# cs301_template.net
KiCad netlist of a schematic drawn in Altium Designer
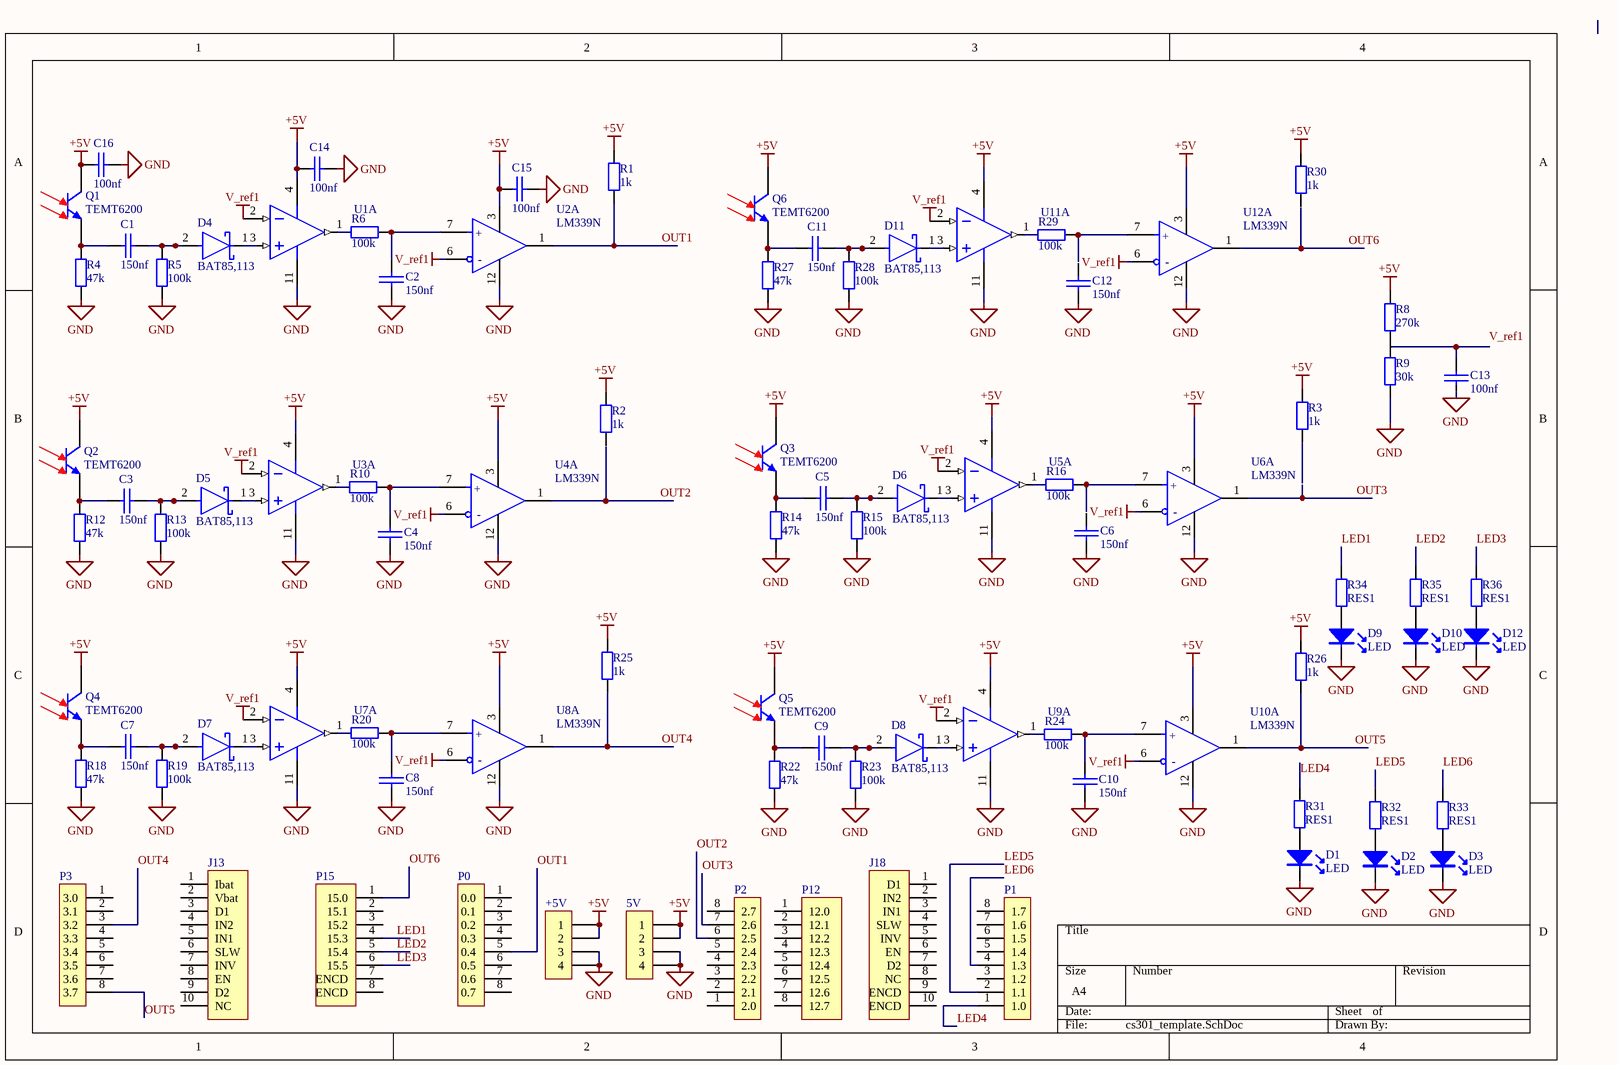
[diagram p0: cs301_template.SchDoc]

(export (version "E")
  (design (tool "Eeschema 10.0.6"))
  (components
    (comp (ref "+5V")
      (value "5V")
      (footprint "IDC4")
      (description "Connector")
      (libsource (lib "Miscellaneous Devices") (part "CON4"))
    )
    (comp (ref "5V")
      (value "5V")
      (footprint "IDC4")
      (description "Connector")
      (libsource (lib "Miscellaneous Devices") (part "CON4"))
    )
    (comp (ref "C1")
      (value "150nf")
      (footprint "CCAP-5P0")
      (description "TH ceramic capacitor with 5mm pitch")
      (libsource (lib "COMSYS301_2025") (part "CerCap_TH_5P0"))
    )
    (comp (ref "C2")
      (value "150nf")
      (footprint "CCAP-5P0")
      (description "TH ceramic capacitor with 5mm pitch")
      (libsource (lib "COMSYS301_2025") (part "CerCap_TH_5P0"))
    )
    (comp (ref "C3")
      (value "150nf")
      (footprint "CCAP-5P0")
      (description "TH ceramic capacitor with 5mm pitch")
      (libsource (lib "COMSYS301_2025") (part "CerCap_TH_5P0"))
    )
    (comp (ref "C4")
      (value "150nf")
      (footprint "CCAP-5P0")
      (description "TH ceramic capacitor with 5mm pitch")
      (libsource (lib "COMSYS301_2025") (part "CerCap_TH_5P0"))
    )
    (comp (ref "C5")
      (value "150nf")
      (footprint "CCAP-5P0")
      (description "TH ceramic capacitor with 5mm pitch")
      (libsource (lib "COMSYS301_2025") (part "CerCap_TH_5P0"))
    )
    (comp (ref "C6")
      (value "150nf")
      (footprint "CCAP-5P0")
      (description "TH ceramic capacitor with 5mm pitch")
      (libsource (lib "COMSYS301_2025") (part "CerCap_TH_5P0"))
    )
    (comp (ref "C7")
      (value "150nf")
      (footprint "CCAP-5P0")
      (description "TH ceramic capacitor with 5mm pitch")
      (libsource (lib "COMSYS301_2025") (part "CerCap_TH_5P0"))
    )
    (comp (ref "C8")
      (value "150nf")
      (footprint "CCAP-5P0")
      (description "TH ceramic capacitor with 5mm pitch")
      (libsource (lib "COMSYS301_2025") (part "CerCap_TH_5P0"))
    )
    (comp (ref "C9")
      (value "150nf")
      (footprint "CCAP-5P0")
      (description "TH ceramic capacitor with 5mm pitch")
      (libsource (lib "COMSYS301_2025") (part "CerCap_TH_5P0"))
    )
    (comp (ref "C10")
      (value "150nf")
      (footprint "CCAP-5P0")
      (description "TH ceramic capacitor with 5mm pitch")
      (libsource (lib "COMSYS301_2025") (part "CerCap_TH_5P0"))
    )
    (comp (ref "C11")
      (value "150nf")
      (footprint "CCAP-5P0")
      (description "TH ceramic capacitor with 5mm pitch")
      (libsource (lib "COMSYS301_2025") (part "CerCap_TH_5P0"))
    )
    (comp (ref "C12")
      (value "150nf")
      (footprint "CCAP-5P0")
      (description "TH ceramic capacitor with 5mm pitch")
      (libsource (lib "COMSYS301_2025") (part "CerCap_TH_5P0"))
    )
    (comp (ref "C13")
      (value "100nf")
      (footprint "CCAP-5P0")
      (description "TH ceramic capacitor with 5mm pitch")
      (libsource (lib "COMSYS301_2025") (part "CerCap_TH_5P0"))
    )
    (comp (ref "C14")
      (value "100nf")
      (footprint "CCAP-5P0")
      (description "TH ceramic capacitor with 5mm pitch")
      (libsource (lib "COMSYS301_2025") (part "CerCap_TH_5P0"))
    )
    (comp (ref "C15")
      (value "100nf")
      (footprint "CCAP-5P0")
      (description "TH ceramic capacitor with 5mm pitch")
      (libsource (lib "COMSYS301_2025") (part "CerCap_TH_5P0"))
    )
    (comp (ref "C16")
      (value "100nf")
      (footprint "CCAP-5P0")
      (description "TH ceramic capacitor with 5mm pitch")
      (libsource (lib "COMSYS301_2025") (part "CerCap_TH_5P0"))
    )
    (comp (ref "D1") (value "LED") (footprint "LED0.1/5MM") (libsource (lib "COMSYS301_2013") (part "LED")))
    (comp (ref "D2") (value "LED") (footprint "LED0.1/5MM") (libsource (lib "COMSYS301_2013") (part "LED")))
    (comp (ref "D3") (value "LED") (footprint "LED0.1/5MM") (libsource (lib "COMSYS301_2013") (part "LED")))
    (comp (ref "D4")
      (value "BAT85,113")
      (footprint "FP-SOD68-MFG")
      (description "DIODE SCHOTTKY 30V 200MA DO34")
      (libsource (lib "Components - 18.08.25 - 15.16") (part "CMP-14398-000042-1"))
    )
    (comp (ref "D5")
      (value "BAT85,113")
      (footprint "FP-SOD68-MFG")
      (description "DIODE SCHOTTKY 30V 200MA DO34")
      (libsource (lib "Components - 18.08.25 - 15.16") (part "CMP-14398-000042-1"))
    )
    (comp (ref "D6")
      (value "BAT85,113")
      (footprint "FP-SOD68-MFG")
      (description "DIODE SCHOTTKY 30V 200MA DO34")
      (libsource (lib "Components - 18.08.25 - 15.16") (part "CMP-14398-000042-1"))
    )
    (comp (ref "D7")
      (value "BAT85,113")
      (footprint "FP-SOD68-MFG")
      (description "DIODE SCHOTTKY 30V 200MA DO34")
      (libsource (lib "Components - 18.08.25 - 15.16") (part "CMP-14398-000042-1"))
    )
    (comp (ref "D8")
      (value "BAT85,113")
      (footprint "FP-SOD68-MFG")
      (description "DIODE SCHOTTKY 30V 200MA DO34")
      (libsource (lib "Components - 18.08.25 - 15.16") (part "CMP-14398-000042-1"))
    )
    (comp (ref "D9") (value "LED") (footprint "LED0.1/5MM") (libsource (lib "COMSYS301_2013") (part "LED")))
    (comp (ref "D10") (value "LED") (footprint "LED0.1/5MM") (libsource (lib "COMSYS301_2013") (part "LED")))
    (comp (ref "D11")
      (value "BAT85,113")
      (footprint "FP-SOD68-MFG")
      (description "DIODE SCHOTTKY 30V 200MA DO34")
      (libsource (lib "Components - 18.08.25 - 15.16") (part "CMP-14398-000042-1"))
    )
    (comp (ref "D12") (value "LED") (footprint "LED0.1/5MM") (libsource (lib "COMSYS301_2013") (part "LED")))
    (comp (ref "J13")
      (value "CON10")
      (footprint "idc10")
      (description "Connector")
      (libsource (lib "Miscellaneous Devices") (part "CON10"))
    )
    (comp (ref "J18")
      (value "CON10")
      (footprint "IDC10")
      (description "Connector")
      (libsource (lib "") (part "CON10_1"))
    )
    (comp (ref "P0")
      (value "P0")
      (footprint "idc8")
      (description "Connector")
      (libsource (lib "Miscellaneous Devices") (part "CON8"))
    )
    (comp (ref "P1")
      (value "P1")
      (footprint "idc8")
      (description "Connector")
      (libsource (lib "") (part "CON8_2"))
    )
    (comp (ref "P2")
      (value "P2")
      (footprint "idc8")
      (description "Connector")
      (libsource (lib "") (part "CON8_1"))
    )
    (comp (ref "P3")
      (value "P3")
      (footprint "idc8")
      (description "Connector")
      (libsource (lib "Miscellaneous Devices") (part "CON8"))
    )
    (comp (ref "P12")
      (value "P12")
      (footprint "idc8")
      (description "Connector")
      (libsource (lib "") (part "CON8_1_1"))
    )
    (comp (ref "P15")
      (value "P15")
      (footprint "idc8")
      (description "Connector")
      (libsource (lib "Miscellaneous Devices") (part "CON8_1"))
    )
    (comp (ref "Q1")
      (value "TEMT6200")
      (footprint "VEMT3700")
      (description "Silicon NPN Phototransistor")
      (libsource (lib "COMSYS301_2025") (part "VEMT3700"))
    )
    (comp (ref "Q2")
      (value "TEMT6200")
      (footprint "VEMT3700")
      (description "Silicon NPN Phototransistor")
      (libsource (lib "COMSYS301_2025") (part "VEMT3700"))
    )
    (comp (ref "Q3")
      (value "TEMT6200")
      (footprint "VEMT3700")
      (description "Silicon NPN Phototransistor")
      (libsource (lib "COMSYS301_2025") (part "VEMT3700"))
    )
    (comp (ref "Q4")
      (value "TEMT6200")
      (footprint "VEMT3700")
      (description "Silicon NPN Phototransistor")
      (libsource (lib "COMSYS301_2025") (part "VEMT3700"))
    )
    (comp (ref "Q5")
      (value "TEMT6200")
      (footprint "VEMT3700")
      (description "Silicon NPN Phototransistor")
      (libsource (lib "COMSYS301_2025") (part "VEMT3700"))
    )
    (comp (ref "Q6")
      (value "TEMT6200")
      (footprint "VEMT3700")
      (description "Silicon NPN Phototransistor")
      (libsource (lib "COMSYS301_2025") (part "VEMT3700"))
    )
    (comp (ref "R1")
      (value "1k")
      (footprint "AXIAL-0.4")
      (description "Through hole resistor")
      (fields (field (name "PUBLISHER") "Altium Limited"))
      (libsource (lib "CS301_Library") (part "Res_TH_0AX4"))
    )
    (comp (ref "R2")
      (value "1k")
      (footprint "AXIAL-0.4")
      (description "Through hole resistor")
      (fields (field (name "PUBLISHER") "Altium Limited"))
      (libsource (lib "CS301_Library") (part "Res_TH_0AX4"))
    )
    (comp (ref "R3")
      (value "1k")
      (footprint "AXIAL-0.4")
      (description "Through hole resistor")
      (fields (field (name "PUBLISHER") "Altium Limited"))
      (libsource (lib "CS301_Library") (part "Res_TH_0AX4"))
    )
    (comp (ref "R4")
      (value "47k")
      (footprint "AXIAL-0.4")
      (description "Through hole resistor")
      (fields (field (name "PUBLISHER") "Altium Limited"))
      (libsource (lib "COMSYS301_2025") (part "Res_TH_0AX4"))
    )
    (comp (ref "R5")
      (value "100k")
      (footprint "AXIAL-0.4")
      (description "Through hole resistor")
      (fields (field (name "PUBLISHER") "Altium Limited"))
      (libsource (lib "COMSYS301_2025") (part "Res_TH_0AX4"))
    )
    (comp (ref "R6")
      (value "100k")
      (footprint "AXIAL-0.4")
      (description "Through hole resistor")
      (fields (field (name "PUBLISHER") "Altium Limited"))
      (libsource (lib "") (part "Res_TH_0AX4_1"))
    )
    (comp (ref "R8")
      (value "270k")
      (footprint "AXIAL-0.4")
      (description "Through hole resistor")
      (fields (field (name "PUBLISHER") "Altium Limited"))
      (libsource (lib "") (part "Res_TH_0AX4_2"))
    )
    (comp (ref "R9")
      (value "30k")
      (footprint "AXIAL-0.4")
      (description "Through hole resistor")
      (fields (field (name "PUBLISHER") "Altium Limited"))
      (libsource (lib "") (part "Res_TH_0AX4_2"))
    )
    (comp (ref "R10")
      (value "100k")
      (footprint "AXIAL-0.4")
      (description "Through hole resistor")
      (fields (field (name "PUBLISHER") "Altium Limited"))
      (libsource (lib "") (part "Res_TH_0AX4_1"))
    )
    (comp (ref "R12")
      (value "47k")
      (footprint "AXIAL-0.4")
      (description "Through hole resistor")
      (fields (field (name "PUBLISHER") "Altium Limited"))
      (libsource (lib "COMSYS301_2025") (part "Res_TH_0AX4"))
    )
    (comp (ref "R13")
      (value "100k")
      (footprint "AXIAL-0.4")
      (description "Through hole resistor")
      (fields (field (name "PUBLISHER") "Altium Limited"))
      (libsource (lib "COMSYS301_2025") (part "Res_TH_0AX4"))
    )
    (comp (ref "R14")
      (value "47k")
      (footprint "AXIAL-0.4")
      (description "Through hole resistor")
      (fields (field (name "PUBLISHER") "Altium Limited"))
      (libsource (lib "COMSYS301_2025") (part "Res_TH_0AX4"))
    )
    (comp (ref "R15")
      (value "100k")
      (footprint "AXIAL-0.4")
      (description "Through hole resistor")
      (fields (field (name "PUBLISHER") "Altium Limited"))
      (libsource (lib "COMSYS301_2025") (part "Res_TH_0AX4"))
    )
    (comp (ref "R16")
      (value "100k")
      (footprint "AXIAL-0.4")
      (description "Through hole resistor")
      (fields (field (name "PUBLISHER") "Altium Limited"))
      (libsource (lib "") (part "Res_TH_0AX4_1"))
    )
    (comp (ref "R18")
      (value "47k")
      (footprint "AXIAL-0.4")
      (description "Through hole resistor")
      (fields (field (name "PUBLISHER") "Altium Limited"))
      (libsource (lib "COMSYS301_2025") (part "Res_TH_0AX4"))
    )
    (comp (ref "R19")
      (value "100k")
      (footprint "AXIAL-0.4")
      (description "Through hole resistor")
      (fields (field (name "PUBLISHER") "Altium Limited"))
      (libsource (lib "COMSYS301_2025") (part "Res_TH_0AX4"))
    )
    (comp (ref "R20")
      (value "100k")
      (footprint "AXIAL-0.4")
      (description "Through hole resistor")
      (fields (field (name "PUBLISHER") "Altium Limited"))
      (libsource (lib "") (part "Res_TH_0AX4_1"))
    )
    (comp (ref "R22")
      (value "47k")
      (footprint "AXIAL-0.4")
      (description "Through hole resistor")
      (fields (field (name "PUBLISHER") "Altium Limited"))
      (libsource (lib "COMSYS301_2025") (part "Res_TH_0AX4"))
    )
    (comp (ref "R23")
      (value "100k")
      (footprint "AXIAL-0.4")
      (description "Through hole resistor")
      (fields (field (name "PUBLISHER") "Altium Limited"))
      (libsource (lib "COMSYS301_2025") (part "Res_TH_0AX4"))
    )
    (comp (ref "R24")
      (value "100k")
      (footprint "AXIAL-0.4")
      (description "Through hole resistor")
      (fields (field (name "PUBLISHER") "Altium Limited"))
      (libsource (lib "") (part "Res_TH_0AX4_1"))
    )
    (comp (ref "R25")
      (value "1k")
      (footprint "AXIAL-0.4")
      (description "Through hole resistor")
      (fields (field (name "PUBLISHER") "Altium Limited"))
      (libsource (lib "CS301_Library") (part "Res_TH_0AX4"))
    )
    (comp (ref "R26")
      (value "1k")
      (footprint "AXIAL-0.4")
      (description "Through hole resistor")
      (fields (field (name "PUBLISHER") "Altium Limited"))
      (libsource (lib "CS301_Library") (part "Res_TH_0AX4"))
    )
    (comp (ref "R27")
      (value "47k")
      (footprint "AXIAL-0.4")
      (description "Through hole resistor")
      (fields (field (name "PUBLISHER") "Altium Limited"))
      (libsource (lib "COMSYS301_2025") (part "Res_TH_0AX4"))
    )
    (comp (ref "R28")
      (value "100k")
      (footprint "AXIAL-0.4")
      (description "Through hole resistor")
      (fields (field (name "PUBLISHER") "Altium Limited"))
      (libsource (lib "COMSYS301_2025") (part "Res_TH_0AX4"))
    )
    (comp (ref "R29")
      (value "100k")
      (footprint "AXIAL-0.4")
      (description "Through hole resistor")
      (fields (field (name "PUBLISHER") "Altium Limited"))
      (libsource (lib "") (part "Res_TH_0AX4_1"))
    )
    (comp (ref "R30")
      (value "1k")
      (footprint "AXIAL-0.4")
      (description "Through hole resistor")
      (fields (field (name "PUBLISHER") "Altium Limited"))
      (libsource (lib "CS301_Library") (part "Res_TH_0AX4"))
    )
    (comp (ref "R31")
      (value "RES1")
      (footprint "AXIAL-0.4")
      (description "Through hole resistor")
      (fields (field (name "PUBLISHER") "Altium Limited"))
      (libsource (lib "CS301_Library") (part "Res_TH_0AX4"))
    )
    (comp (ref "R32")
      (value "RES1")
      (footprint "AXIAL-0.4")
      (description "Through hole resistor")
      (fields (field (name "PUBLISHER") "Altium Limited"))
      (libsource (lib "CS301_Library") (part "Res_TH_0AX4"))
    )
    (comp (ref "R33")
      (value "RES1")
      (footprint "AXIAL-0.4")
      (description "Through hole resistor")
      (fields (field (name "PUBLISHER") "Altium Limited"))
      (libsource (lib "CS301_Library") (part "Res_TH_0AX4"))
    )
    (comp (ref "R34")
      (value "RES1")
      (footprint "AXIAL-0.4")
      (description "Through hole resistor")
      (fields (field (name "PUBLISHER") "Altium Limited"))
      (libsource (lib "CS301_Library") (part "Res_TH_0AX4"))
    )
    (comp (ref "R35")
      (value "RES1")
      (footprint "AXIAL-0.4")
      (description "Through hole resistor")
      (fields (field (name "PUBLISHER") "Altium Limited"))
      (libsource (lib "CS301_Library") (part "Res_TH_0AX4"))
    )
    (comp (ref "R36")
      (value "RES1")
      (footprint "AXIAL-0.4")
      (description "Through hole resistor")
      (fields (field (name "PUBLISHER") "Altium Limited"))
      (libsource (lib "CS301_Library") (part "Res_TH_0AX4"))
    )
    (comp (ref "U1")
      (value "LM324")
      (footprint "DIP-14")
      (description "IC OPAMP GP 14DIP")
      (fields
        (field (name "MANUFACTURER") "ON Semiconductor")
        (field (name "MANUFACTURER PART NUMBER") "LM324N")
      )
      (libsource (lib "COMSYS301_2025") (part "LM324N_TH_DIP16"))
    )
    (comp (ref "U2")
      (value "LM339N")
      (footprint "FP-N0014A-MFG")
      (description "IC QUAD DIFF COMPARATOR 14-DIP")
      (libsource (lib "Components - 18.08.25 - 15.06") (part "CMP-0055-00143-4"))
    )
    (comp (ref "U3")
      (value "LM324")
      (footprint "DIP-14")
      (description "IC OPAMP GP 14DIP")
      (fields
        (field (name "MANUFACTURER") "ON Semiconductor")
        (field (name "MANUFACTURER PART NUMBER") "LM324N")
      )
      (libsource (lib "COMSYS301_2025") (part "LM324N_TH_DIP16"))
    )
    (comp (ref "U4")
      (value "LM339N")
      (footprint "FP-N0014A-MFG")
      (description "IC QUAD DIFF COMPARATOR 14-DIP")
      (libsource (lib "Components - 18.08.25 - 15.06") (part "CMP-0055-00143-4"))
    )
    (comp (ref "U5")
      (value "LM324")
      (footprint "DIP-14")
      (description "IC OPAMP GP 14DIP")
      (fields
        (field (name "MANUFACTURER") "ON Semiconductor")
        (field (name "MANUFACTURER PART NUMBER") "LM324N")
      )
      (libsource (lib "COMSYS301_2025") (part "LM324N_TH_DIP16"))
    )
    (comp (ref "U6")
      (value "LM339N")
      (footprint "FP-N0014A-MFG")
      (description "IC QUAD DIFF COMPARATOR 14-DIP")
      (libsource (lib "Components - 18.08.25 - 15.06") (part "CMP-0055-00143-4"))
    )
    (comp (ref "U7")
      (value "LM324")
      (footprint "DIP-14")
      (description "IC OPAMP GP 14DIP")
      (fields
        (field (name "MANUFACTURER") "ON Semiconductor")
        (field (name "MANUFACTURER PART NUMBER") "LM324N")
      )
      (libsource (lib "COMSYS301_2025") (part "LM324N_TH_DIP16"))
    )
    (comp (ref "U8")
      (value "LM339N")
      (footprint "FP-N0014A-MFG")
      (description "IC QUAD DIFF COMPARATOR 14-DIP")
      (libsource (lib "Components - 18.08.25 - 15.06") (part "CMP-0055-00143-4"))
    )
    (comp (ref "U9")
      (value "LM324")
      (footprint "DIP-14")
      (description "IC OPAMP GP 14DIP")
      (fields
        (field (name "MANUFACTURER") "ON Semiconductor")
        (field (name "MANUFACTURER PART NUMBER") "LM324N")
      )
      (libsource (lib "COMSYS301_2025") (part "LM324N_TH_DIP16"))
    )
    (comp (ref "U10")
      (value "LM339N")
      (footprint "FP-N0014A-MFG")
      (description "IC QUAD DIFF COMPARATOR 14-DIP")
      (libsource (lib "Components - 18.08.25 - 15.06") (part "CMP-0055-00143-4"))
    )
    (comp (ref "U11")
      (value "LM324")
      (footprint "DIP-14")
      (description "IC OPAMP GP 14DIP")
      (fields
        (field (name "MANUFACTURER") "ON Semiconductor")
        (field (name "MANUFACTURER PART NUMBER") "LM324N")
      )
      (libsource (lib "COMSYS301_2025") (part "LM324N_TH_DIP16"))
    )
    (comp (ref "U12")
      (value "LM339N")
      (footprint "FP-N0014A-MFG")
      (description "IC QUAD DIFF COMPARATOR 14-DIP")
      (libsource (lib "Components - 18.08.25 - 15.06") (part "CMP-0055-00143-4"))
    )
  )
  (nets
    (net (code "1") (name "+5V") (class "Default")
      (node (ref "+5V") (pin "1") (pinfunction "1_1") (pintype "passive"))
      (node (ref "+5V") (pin "2") (pinfunction "2_2") (pintype "passive"))
      (node (ref "5V") (pin "1") (pinfunction "1_1") (pintype "passive"))
      (node (ref "5V") (pin "2") (pinfunction "2_2") (pintype "passive"))
      (node (ref "C14") (pin "1") (pinfunction "1_1") (pintype "passive"))
      (node (ref "C15") (pin "1") (pinfunction "1_1") (pintype "passive"))
      (node (ref "C16") (pin "1") (pinfunction "1_1") (pintype "passive"))
      (node (ref "Q1") (pin "1") (pinfunction "C_1") (pintype "passive"))
      (node (ref "Q2") (pin "1") (pinfunction "C_1") (pintype "passive"))
      (node (ref "Q3") (pin "1") (pinfunction "C_1") (pintype "passive"))
      (node (ref "Q4") (pin "1") (pinfunction "C_1") (pintype "passive"))
      (node (ref "Q5") (pin "1") (pinfunction "C_1") (pintype "passive"))
      (node (ref "Q6") (pin "1") (pinfunction "C_1") (pintype "passive"))
      (node (ref "R1") (pin "2") (pinfunction "2_2") (pintype "passive"))
      (node (ref "R2") (pin "2") (pinfunction "2_2") (pintype "passive"))
      (node (ref "R25") (pin "2") (pinfunction "2_2") (pintype "passive"))
      (node (ref "R26") (pin "2") (pinfunction "2_2") (pintype "passive"))
      (node (ref "R3") (pin "2") (pinfunction "2_2") (pintype "passive"))
      (node (ref "R30") (pin "2") (pinfunction "2_2") (pintype "passive"))
      (node (ref "R8") (pin "1") (pinfunction "1_1") (pintype "passive"))
      (node (ref "U1") (pin "4") (pinfunction "VDD_4") (pintype "power_in"))
      (node (ref "U10") (pin "3") (pinfunction "VCC_3") (pintype "power_in"))
      (node (ref "U11") (pin "4") (pinfunction "VDD_4") (pintype "power_in"))
      (node (ref "U12") (pin "3") (pinfunction "VCC_3") (pintype "power_in"))
      (node (ref "U2") (pin "3") (pinfunction "VCC_3") (pintype "power_in"))
      (node (ref "U3") (pin "4") (pinfunction "VDD_4") (pintype "power_in"))
      (node (ref "U4") (pin "3") (pinfunction "VCC_3") (pintype "power_in"))
      (node (ref "U5") (pin "4") (pinfunction "VDD_4") (pintype "power_in"))
      (node (ref "U6") (pin "3") (pinfunction "VCC_3") (pintype "power_in"))
      (node (ref "U7") (pin "4") (pinfunction "VDD_4") (pintype "power_in"))
      (node (ref "U8") (pin "3") (pinfunction "VCC_3") (pintype "power_in"))
      (node (ref "U9") (pin "4") (pinfunction "VDD_4") (pintype "power_in"))
    )
    (net (code "2") (name "/LED1") (class "Default")
      (node (ref "P15") (pin "4") (pinfunction "15.3_4") (pintype "passive"))
      (node (ref "R34") (pin "2") (pinfunction "2_2") (pintype "passive"))
    )
    (net (code "3") (name "/LED2") (class "Default")
      (node (ref "P15") (pin "5") (pinfunction "15.4_5") (pintype "passive"))
      (node (ref "R35") (pin "2") (pinfunction "2_2") (pintype "passive"))
    )
    (net (code "4") (name "/LED3") (class "Default")
      (node (ref "P15") (pin "6") (pinfunction "15.5_6") (pintype "passive"))
      (node (ref "R36") (pin "2") (pinfunction "2_2") (pintype "passive"))
    )
    (net (code "5") (name "/LED4") (class "Default")
      (node (ref "P1") (pin "1") (pinfunction "1.0_1") (pintype "passive"))
      (node (ref "R31") (pin "2") (pinfunction "2_2") (pintype "passive"))
    )
    (net (code "6") (name "/LED5") (class "Default")
      (node (ref "P1") (pin "2") (pinfunction "1.1_2") (pintype "passive"))
      (node (ref "R32") (pin "2") (pinfunction "2_2") (pintype "passive"))
    )
    (net (code "7") (name "/LED6") (class "Default")
      (node (ref "P1") (pin "4") (pinfunction "1.3_4") (pintype "passive"))
      (node (ref "R33") (pin "2") (pinfunction "2_2") (pintype "passive"))
    )
    (net (code "8") (name "/OUT1") (class "Default")
      (node (ref "P0") (pin "5") (pinfunction "3.4_5") (pintype "passive"))
      (node (ref "R1") (pin "1") (pinfunction "1_1") (pintype "passive"))
      (node (ref "U2") (pin "1") (pinfunction "1OUT_1") (pintype "passive"))
    )
    (net (code "9") (name "/OUT2") (class "Default")
      (node (ref "P2") (pin "6") (pinfunction "2.5_6") (pintype "passive"))
      (node (ref "U4") (pin "1") (pinfunction "1OUT_1") (pintype "passive"))
    )
    (net (code "10") (name "/OUT3") (class "Default")
      (node (ref "P2") (pin "7") (pinfunction "2.6_7") (pintype "passive"))
      (node (ref "U6") (pin "1") (pinfunction "1OUT_1") (pintype "passive"))
    )
    (net (code "11") (name "/OUT4") (class "Default")
      (node (ref "P3") (pin "3") (pinfunction "3.2_3") (pintype "passive"))
      (node (ref "R25") (pin "1") (pinfunction "1_1") (pintype "passive"))
      (node (ref "U8") (pin "1") (pinfunction "1OUT_1") (pintype "passive"))
    )
    (net (code "12") (name "/OUT5") (class "Default")
      (node (ref "P3") (pin "8") (pinfunction "3.7_8") (pintype "passive"))
      (node (ref "R26") (pin "1") (pinfunction "1_1") (pintype "passive"))
      (node (ref "U10") (pin "1") (pinfunction "1OUT_1") (pintype "passive"))
    )
    (net (code "13") (name "/OUT6") (class "Default")
      (node (ref "P15") (pin "1") (pinfunction "15.0_1") (pintype "passive"))
      (node (ref "U12") (pin "1") (pinfunction "1OUT_1") (pintype "passive"))
    )
    (net (code "14") (name "GND") (class "Default")
      (node (ref "+5V") (pin "3") (pinfunction "3_3") (pintype "passive"))
      (node (ref "+5V") (pin "4") (pinfunction "4_4") (pintype "passive"))
      (node (ref "5V") (pin "3") (pinfunction "3_3") (pintype "passive"))
      (node (ref "5V") (pin "4") (pinfunction "4_4") (pintype "passive"))
      (node (ref "C10") (pin "2") (pinfunction "2_2") (pintype "passive"))
      (node (ref "C13") (pin "2") (pinfunction "2_2") (pintype "passive"))
      (node (ref "C14") (pin "2") (pinfunction "2_2") (pintype "passive"))
      (node (ref "C15") (pin "2") (pinfunction "2_2") (pintype "passive"))
      (node (ref "C16") (pin "2") (pinfunction "2_2") (pintype "passive"))
      (node (ref "C2") (pin "2") (pinfunction "2_2") (pintype "passive"))
      (node (ref "C4") (pin "2") (pinfunction "2_2") (pintype "passive"))
      (node (ref "C8") (pin "2") (pinfunction "2_2") (pintype "passive"))
      (node (ref "D1") (pin "K") (pinfunction "2_K") (pintype "passive"))
      (node (ref "D10") (pin "K") (pinfunction "2_K") (pintype "passive"))
      (node (ref "D12") (pin "K") (pinfunction "2_K") (pintype "passive"))
      (node (ref "D2") (pin "K") (pinfunction "2_K") (pintype "passive"))
      (node (ref "D3") (pin "K") (pinfunction "2_K") (pintype "passive"))
      (node (ref "D9") (pin "K") (pinfunction "2_K") (pintype "passive"))
      (node (ref "R12") (pin "1") (pinfunction "1_1") (pintype "passive"))
      (node (ref "R13") (pin "1") (pinfunction "1_1") (pintype "passive"))
      (node (ref "R14") (pin "1") (pinfunction "1_1") (pintype "passive"))
      (node (ref "R15") (pin "1") (pinfunction "1_1") (pintype "passive"))
      (node (ref "R18") (pin "1") (pinfunction "1_1") (pintype "passive"))
      (node (ref "R19") (pin "1") (pinfunction "1_1") (pintype "passive"))
      (node (ref "R22") (pin "1") (pinfunction "1_1") (pintype "passive"))
      (node (ref "R23") (pin "1") (pinfunction "1_1") (pintype "passive"))
      (node (ref "R27") (pin "1") (pinfunction "1_1") (pintype "passive"))
      (node (ref "R28") (pin "1") (pinfunction "1_1") (pintype "passive"))
      (node (ref "R4") (pin "1") (pinfunction "1_1") (pintype "passive"))
      (node (ref "R5") (pin "1") (pinfunction "1_1") (pintype "passive"))
      (node (ref "R9") (pin "2") (pinfunction "2_2") (pintype "passive"))
      (node (ref "U1") (pin "11") (pinfunction "VSS_11") (pintype "power_in"))
      (node (ref "U10") (pin "12") (pinfunction "GND_12") (pintype "power_in"))
      (node (ref "U11") (pin "11") (pinfunction "VSS_11") (pintype "power_in"))
      (node (ref "U12") (pin "12") (pinfunction "GND_12") (pintype "power_in"))
      (node (ref "U2") (pin "12") (pinfunction "GND_12") (pintype "power_in"))
      (node (ref "U3") (pin "11") (pinfunction "VSS_11") (pintype "power_in"))
      (node (ref "U4") (pin "12") (pinfunction "GND_12") (pintype "power_in"))
      (node (ref "U5") (pin "11") (pinfunction "VSS_11") (pintype "power_in"))
      (node (ref "U6") (pin "12") (pinfunction "GND_12") (pintype "power_in"))
      (node (ref "U7") (pin "11") (pinfunction "VSS_11") (pintype "power_in"))
      (node (ref "U8") (pin "12") (pinfunction "GND_12") (pintype "power_in"))
      (node (ref "U9") (pin "11") (pinfunction "VSS_11") (pintype "power_in"))
    )
    (net (code "15") (name "Net-(D1-1)") (class "Default")
      (node (ref "D1") (pin "A") (pinfunction "1_A") (pintype "passive"))
      (node (ref "R31") (pin "1") (pinfunction "1_1") (pintype "passive"))
    )
    (net (code "16") (name "Net-(D2-1)") (class "Default")
      (node (ref "D2") (pin "A") (pinfunction "1_A") (pintype "passive"))
      (node (ref "R32") (pin "1") (pinfunction "1_1") (pintype "passive"))
    )
    (net (code "17") (name "Net-(D3-1)") (class "Default")
      (node (ref "D3") (pin "A") (pinfunction "1_A") (pintype "passive"))
      (node (ref "R33") (pin "1") (pinfunction "1_1") (pintype "passive"))
    )
    (net (code "18") (name "Net-(D4-A)") (class "Default")
      (node (ref "C1") (pin "2") (pinfunction "2_2") (pintype "passive"))
      (node (ref "D4") (pin "2") (pinfunction "A_2") (pintype "passive"))
      (node (ref "R5") (pin "2") (pinfunction "2_2") (pintype "passive"))
    )
    (net (code "19") (name "Net-(D4-C)") (class "Default")
      (node (ref "D4") (pin "1") (pinfunction "C_1") (pintype "passive"))
      (node (ref "U1") (pin "3") (pinfunction "VINA+_3") (pintype "input"))
    )
    (net (code "20") (name "Net-(D5-A)") (class "Default")
      (node (ref "C3") (pin "2") (pinfunction "2_2") (pintype "passive"))
      (node (ref "D5") (pin "2") (pinfunction "A_2") (pintype "passive"))
      (node (ref "R13") (pin "2") (pinfunction "2_2") (pintype "passive"))
    )
    (net (code "21") (name "Net-(D5-C)") (class "Default")
      (node (ref "D5") (pin "1") (pinfunction "C_1") (pintype "passive"))
      (node (ref "U3") (pin "3") (pinfunction "VINA+_3") (pintype "input"))
    )
    (net (code "22") (name "Net-(D6-A)") (class "Default")
      (node (ref "C5") (pin "2") (pinfunction "2_2") (pintype "passive"))
      (node (ref "D6") (pin "2") (pinfunction "A_2") (pintype "passive"))
      (node (ref "R15") (pin "2") (pinfunction "2_2") (pintype "passive"))
    )
    (net (code "23") (name "Net-(D6-C)") (class "Default")
      (node (ref "D6") (pin "1") (pinfunction "C_1") (pintype "passive"))
      (node (ref "U5") (pin "3") (pinfunction "VINA+_3") (pintype "input"))
    )
    (net (code "24") (name "Net-(D7-A)") (class "Default")
      (node (ref "C7") (pin "2") (pinfunction "2_2") (pintype "passive"))
      (node (ref "D7") (pin "2") (pinfunction "A_2") (pintype "passive"))
      (node (ref "R19") (pin "2") (pinfunction "2_2") (pintype "passive"))
    )
    (net (code "25") (name "Net-(D7-C)") (class "Default")
      (node (ref "D7") (pin "1") (pinfunction "C_1") (pintype "passive"))
      (node (ref "U7") (pin "3") (pinfunction "VINA+_3") (pintype "input"))
    )
    (net (code "26") (name "Net-(D8-A)") (class "Default")
      (node (ref "C9") (pin "2") (pinfunction "2_2") (pintype "passive"))
      (node (ref "D8") (pin "2") (pinfunction "A_2") (pintype "passive"))
      (node (ref "R23") (pin "2") (pinfunction "2_2") (pintype "passive"))
    )
    (net (code "27") (name "Net-(D8-C)") (class "Default")
      (node (ref "D8") (pin "1") (pinfunction "C_1") (pintype "passive"))
      (node (ref "U9") (pin "3") (pinfunction "VINA+_3") (pintype "input"))
    )
    (net (code "28") (name "Net-(D9-1)") (class "Default")
      (node (ref "D9") (pin "A") (pinfunction "1_A") (pintype "passive"))
      (node (ref "R34") (pin "1") (pinfunction "1_1") (pintype "passive"))
    )
    (net (code "29") (name "Net-(D10-1)") (class "Default")
      (node (ref "D10") (pin "A") (pinfunction "1_A") (pintype "passive"))
      (node (ref "R35") (pin "1") (pinfunction "1_1") (pintype "passive"))
    )
    (net (code "30") (name "Net-(D11-A)") (class "Default")
      (node (ref "C11") (pin "2") (pinfunction "2_2") (pintype "passive"))
      (node (ref "D11") (pin "2") (pinfunction "A_2") (pintype "passive"))
      (node (ref "R28") (pin "2") (pinfunction "2_2") (pintype "passive"))
    )
    (net (code "31") (name "Net-(D11-C)") (class "Default")
      (node (ref "D11") (pin "1") (pinfunction "C_1") (pintype "passive"))
      (node (ref "U11") (pin "3") (pinfunction "VINA+_3") (pintype "input"))
    )
    (net (code "32") (name "Net-(D12-1)") (class "Default")
      (node (ref "D12") (pin "A") (pinfunction "1_A") (pintype "passive"))
      (node (ref "R36") (pin "1") (pinfunction "1_1") (pintype "passive"))
    )
    (net (code "33") (name "Net-(Q1-E)") (class "Default")
      (node (ref "C1") (pin "1") (pinfunction "1_1") (pintype "passive"))
      (node (ref "Q1") (pin "2") (pinfunction "E_2") (pintype "passive"))
      (node (ref "R4") (pin "2") (pinfunction "2_2") (pintype "passive"))
    )
    (net (code "34") (name "Net-(Q2-E)") (class "Default")
      (node (ref "C3") (pin "1") (pinfunction "1_1") (pintype "passive"))
      (node (ref "Q2") (pin "2") (pinfunction "E_2") (pintype "passive"))
      (node (ref "R12") (pin "2") (pinfunction "2_2") (pintype "passive"))
    )
    (net (code "35") (name "Net-(Q3-E)") (class "Default")
      (node (ref "C5") (pin "1") (pinfunction "1_1") (pintype "passive"))
      (node (ref "Q3") (pin "2") (pinfunction "E_2") (pintype "passive"))
      (node (ref "R14") (pin "2") (pinfunction "2_2") (pintype "passive"))
    )
    (net (code "36") (name "Net-(Q4-E)") (class "Default")
      (node (ref "C7") (pin "1") (pinfunction "1_1") (pintype "passive"))
      (node (ref "Q4") (pin "2") (pinfunction "E_2") (pintype "passive"))
      (node (ref "R18") (pin "2") (pinfunction "2_2") (pintype "passive"))
    )
    (net (code "37") (name "Net-(Q5-E)") (class "Default")
      (node (ref "C9") (pin "1") (pinfunction "1_1") (pintype "passive"))
      (node (ref "Q5") (pin "2") (pinfunction "E_2") (pintype "passive"))
      (node (ref "R22") (pin "2") (pinfunction "2_2") (pintype "passive"))
    )
    (net (code "38") (name "Net-(Q6-E)") (class "Default")
      (node (ref "C11") (pin "1") (pinfunction "1_1") (pintype "passive"))
      (node (ref "Q6") (pin "2") (pinfunction "E_2") (pintype "passive"))
      (node (ref "R27") (pin "2") (pinfunction "2_2") (pintype "passive"))
    )
    (net (code "39") (name "Net-(R8-Pad2)") (class "Default")
      (node (ref "R8") (pin "2") (pinfunction "2_2") (pintype "passive"))
      (node (ref "R9") (pin "1") (pinfunction "1_1") (pintype "passive"))
    )
    (net (code "40") (name "Net-(U1A-VOUTA)") (class "Default")
      (node (ref "R6") (pin "2") (pinfunction "2_2") (pintype "passive"))
      (node (ref "U1") (pin "1") (pinfunction "VOUTA_1") (pintype "output"))
    )
    (net (code "41") (name "Net-(U2A-1IN+)") (class "Default")
      (node (ref "C2") (pin "1") (pinfunction "1_1") (pintype "passive"))
      (node (ref "R6") (pin "1") (pinfunction "1_1") (pintype "passive"))
      (node (ref "U2") (pin "7") (pinfunction "1IN+_7") (pintype "tri_state"))
    )
    (net (code "42") (name "Net-(U3A-VOUTA)") (class "Default")
      (node (ref "R10") (pin "2") (pinfunction "2_2") (pintype "passive"))
      (node (ref "U3") (pin "1") (pinfunction "VOUTA_1") (pintype "output"))
    )
    (net (code "43") (name "Net-(U4A-1IN+)") (class "Default")
      (node (ref "C4") (pin "1") (pinfunction "1_1") (pintype "passive"))
      (node (ref "R10") (pin "1") (pinfunction "1_1") (pintype "passive"))
      (node (ref "U4") (pin "7") (pinfunction "1IN+_7") (pintype "tri_state"))
    )
    (net (code "44") (name "Net-(U5A-VOUTA)") (class "Default")
      (node (ref "R16") (pin "2") (pinfunction "2_2") (pintype "passive"))
      (node (ref "U5") (pin "1") (pinfunction "VOUTA_1") (pintype "output"))
    )
    (net (code "45") (name "Net-(U6A-1IN+)") (class "Default")
      (node (ref "R16") (pin "1") (pinfunction "1_1") (pintype "passive"))
      (node (ref "U6") (pin "7") (pinfunction "1IN+_7") (pintype "tri_state"))
    )
    (net (code "46") (name "Net-(U7A-VOUTA)") (class "Default")
      (node (ref "R20") (pin "2") (pinfunction "2_2") (pintype "passive"))
      (node (ref "U7") (pin "1") (pinfunction "VOUTA_1") (pintype "output"))
    )
    (net (code "47") (name "Net-(U8A-1IN+)") (class "Default")
      (node (ref "C8") (pin "1") (pinfunction "1_1") (pintype "passive"))
      (node (ref "R20") (pin "1") (pinfunction "1_1") (pintype "passive"))
      (node (ref "U8") (pin "7") (pinfunction "1IN+_7") (pintype "tri_state"))
    )
    (net (code "48") (name "Net-(U9A-VOUTA)") (class "Default")
      (node (ref "R24") (pin "2") (pinfunction "2_2") (pintype "passive"))
      (node (ref "U9") (pin "1") (pinfunction "VOUTA_1") (pintype "output"))
    )
    (net (code "49") (name "Net-(U10A-1IN+)") (class "Default")
      (node (ref "C10") (pin "1") (pinfunction "1_1") (pintype "passive"))
      (node (ref "R24") (pin "1") (pinfunction "1_1") (pintype "passive"))
      (node (ref "U10") (pin "7") (pinfunction "1IN+_7") (pintype "tri_state"))
    )
    (net (code "50") (name "Net-(U11A-VOUTA)") (class "Default")
      (node (ref "R29") (pin "2") (pinfunction "2_2") (pintype "passive"))
      (node (ref "U11") (pin "1") (pinfunction "VOUTA_1") (pintype "output"))
    )
    (net (code "51") (name "Net-(U12A-1IN+)") (class "Default")
      (node (ref "R29") (pin "1") (pinfunction "1_1") (pintype "passive"))
      (node (ref "U12") (pin "7") (pinfunction "1IN+_7") (pintype "tri_state"))
    )
    (net (code "52") (name "V_ref1") (class "Default")
      (node (ref "U1") (pin "2") (pinfunction "VINA-_2") (pintype "input"))
      (node (ref "U10") (pin "6") (pinfunction "1IN-_6") (pintype "tri_state"))
      (node (ref "U11") (pin "2") (pinfunction "VINA-_2") (pintype "input"))
      (node (ref "U12") (pin "6") (pinfunction "1IN-_6") (pintype "tri_state"))
      (node (ref "U2") (pin "6") (pinfunction "1IN-_6") (pintype "tri_state"))
      (node (ref "U3") (pin "2") (pinfunction "VINA-_2") (pintype "input"))
      (node (ref "U4") (pin "6") (pinfunction "1IN-_6") (pintype "tri_state"))
      (node (ref "U5") (pin "2") (pinfunction "VINA-_2") (pintype "input"))
      (node (ref "U6") (pin "6") (pinfunction "1IN-_6") (pintype "tri_state"))
      (node (ref "U7") (pin "2") (pinfunction "VINA-_2") (pintype "input"))
      (node (ref "U8") (pin "6") (pinfunction "1IN-_6") (pintype "tri_state"))
      (node (ref "U9") (pin "2") (pinfunction "VINA-_2") (pintype "input"))
    )
    (net (code "53") (name "unconnected-(C6-Pad1)") (class "Default")
      (node (ref "C6") (pin "1") (pinfunction "1_1") (pintype "passive"))
    )
    (net (code "54") (name "unconnected-(C6-Pad2)") (class "Default")
      (node (ref "C6") (pin "2") (pinfunction "2_2") (pintype "passive"))
    )
    (net (code "55") (name "unconnected-(C12-Pad1)") (class "Default")
      (node (ref "C12") (pin "1") (pinfunction "1_1") (pintype "passive"))
    )
    (net (code "56") (name "unconnected-(C12-Pad2)") (class "Default")
      (node (ref "C12") (pin "2") (pinfunction "2_2") (pintype "passive"))
    )
    (net (code "57") (name "unconnected-(C13-Pad1)") (class "Default")
      (node (ref "C13") (pin "1") (pinfunction "1_1") (pintype "passive"))
    )
    (net (code "58") (name "unconnected-(J13-D1-Pad3)") (class "Default")
      (node (ref "J13") (pin "3") (pinfunction "D1_3") (pintype "passive"))
    )
    (net (code "59") (name "unconnected-(J13-D2-Pad9)") (class "Default")
      (node (ref "J13") (pin "9") (pinfunction "D2_9") (pintype "passive"))
    )
    (net (code "60") (name "unconnected-(J13-EN-Pad8)") (class "Default")
      (node (ref "J13") (pin "8") (pinfunction "EN_8") (pintype "passive"))
    )
    (net (code "61") (name "unconnected-(J13-IN1-Pad5)") (class "Default")
      (node (ref "J13") (pin "5") (pinfunction "IN1_5") (pintype "passive"))
    )
    (net (code "62") (name "unconnected-(J13-IN2-Pad4)") (class "Default")
      (node (ref "J13") (pin "4") (pinfunction "IN2_4") (pintype "passive"))
    )
    (net (code "63") (name "unconnected-(J13-INV-Pad7)") (class "Default")
      (node (ref "J13") (pin "7") (pinfunction "INV_7") (pintype "passive"))
    )
    (net (code "64") (name "unconnected-(J13-Ibat-Pad1)") (class "Default")
      (node (ref "J13") (pin "1") (pinfunction "Ibat_1") (pintype "passive"))
    )
    (net (code "65") (name "unconnected-(J13-NC-Pad10)") (class "Default")
      (node (ref "J13") (pin "10") (pinfunction "NC_10") (pintype "passive"))
    )
    (net (code "66") (name "unconnected-(J13-SLW-Pad6)") (class "Default")
      (node (ref "J13") (pin "6") (pinfunction "SLW_6") (pintype "passive"))
    )
    (net (code "67") (name "unconnected-(J13-Vbat-Pad2)") (class "Default")
      (node (ref "J13") (pin "2") (pinfunction "Vbat_2") (pintype "passive"))
    )
    (net (code "68") (name "unconnected-(J18-D1-Pad1)") (class "Default")
      (node (ref "J18") (pin "1") (pinfunction "D1_1") (pintype "passive"))
    )
    (net (code "69") (name "unconnected-(J18-D2-Pad7)") (class "Default")
      (node (ref "J18") (pin "7") (pinfunction "D2_7") (pintype "passive"))
    )
    (net (code "70") (name "unconnected-(J18-EN-Pad6)") (class "Default")
      (node (ref "J18") (pin "6") (pinfunction "EN_6") (pintype "passive"))
    )
    (net (code "71") (name "unconnected-(J18-ENCD-Pad9)") (class "Default")
      (node (ref "J18") (pin "9") (pinfunction "ENCD_9") (pintype "passive"))
    )
    (net (code "72") (name "unconnected-(J18-ENCD-Pad10)") (class "Default")
      (node (ref "J18") (pin "10") (pinfunction "ENCD_10") (pintype "passive"))
    )
    (net (code "73") (name "unconnected-(J18-IN1-Pad3)") (class "Default")
      (node (ref "J18") (pin "3") (pinfunction "IN1_3") (pintype "passive"))
    )
    (net (code "74") (name "unconnected-(J18-IN2-Pad2)") (class "Default")
      (node (ref "J18") (pin "2") (pinfunction "IN2_2") (pintype "passive"))
    )
    (net (code "75") (name "unconnected-(J18-INV-Pad5)") (class "Default")
      (node (ref "J18") (pin "5") (pinfunction "INV_5") (pintype "passive"))
    )
    (net (code "76") (name "unconnected-(J18-NC-Pad8)") (class "Default")
      (node (ref "J18") (pin "8") (pinfunction "NC_8") (pintype "passive"))
    )
    (net (code "77") (name "unconnected-(J18-SLW-Pad4)") (class "Default")
      (node (ref "J18") (pin "4") (pinfunction "SLW_4") (pintype "passive"))
    )
    (net (code "78") (name "unconnected-(P0-3.0-Pad1)") (class "Default")
      (node (ref "P0") (pin "1") (pinfunction "3.0_1") (pintype "passive"))
    )
    (net (code "79") (name "unconnected-(P0-3.1-Pad2)") (class "Default")
      (node (ref "P0") (pin "2") (pinfunction "3.1_2") (pintype "passive"))
    )
    (net (code "80") (name "unconnected-(P0-3.2-Pad3)") (class "Default")
      (node (ref "P0") (pin "3") (pinfunction "3.2_3") (pintype "passive"))
    )
    (net (code "81") (name "unconnected-(P0-3.3-Pad4)") (class "Default")
      (node (ref "P0") (pin "4") (pinfunction "3.3_4") (pintype "passive"))
    )
    (net (code "82") (name "unconnected-(P0-3.5-Pad6)") (class "Default")
      (node (ref "P0") (pin "6") (pinfunction "3.5_6") (pintype "passive"))
    )
    (net (code "83") (name "unconnected-(P0-3.6-Pad7)") (class "Default")
      (node (ref "P0") (pin "7") (pinfunction "3.6_7") (pintype "passive"))
    )
    (net (code "84") (name "unconnected-(P0-3.7-Pad8)") (class "Default")
      (node (ref "P0") (pin "8") (pinfunction "3.7_8") (pintype "passive"))
    )
    (net (code "85") (name "unconnected-(P1-1.2-Pad3)") (class "Default")
      (node (ref "P1") (pin "3") (pinfunction "1.2_3") (pintype "passive"))
    )
    (net (code "86") (name "unconnected-(P1-1.4-Pad5)") (class "Default")
      (node (ref "P1") (pin "5") (pinfunction "1.4_5") (pintype "passive"))
    )
    (net (code "87") (name "unconnected-(P1-1.5-Pad6)") (class "Default")
      (node (ref "P1") (pin "6") (pinfunction "1.5_6") (pintype "passive"))
    )
    (net (code "88") (name "unconnected-(P1-1.6-Pad7)") (class "Default")
      (node (ref "P1") (pin "7") (pinfunction "1.6_7") (pintype "passive"))
    )
    (net (code "89") (name "unconnected-(P1-1.7-Pad8)") (class "Default")
      (node (ref "P1") (pin "8") (pinfunction "1.7_8") (pintype "passive"))
    )
    (net (code "90") (name "unconnected-(P2-2.0-Pad1)") (class "Default")
      (node (ref "P2") (pin "1") (pinfunction "2.0_1") (pintype "passive"))
    )
    (net (code "91") (name "unconnected-(P2-2.1-Pad2)") (class "Default")
      (node (ref "P2") (pin "2") (pinfunction "2.1_2") (pintype "passive"))
    )
    (net (code "92") (name "unconnected-(P2-2.2-Pad3)") (class "Default")
      (node (ref "P2") (pin "3") (pinfunction "2.2_3") (pintype "passive"))
    )
    (net (code "93") (name "unconnected-(P2-2.3-Pad4)") (class "Default")
      (node (ref "P2") (pin "4") (pinfunction "2.3_4") (pintype "passive"))
    )
    (net (code "94") (name "unconnected-(P2-2.4-Pad5)") (class "Default")
      (node (ref "P2") (pin "5") (pinfunction "2.4_5") (pintype "passive"))
    )
    (net (code "95") (name "unconnected-(P2-2.7-Pad8)") (class "Default")
      (node (ref "P2") (pin "8") (pinfunction "2.7_8") (pintype "passive"))
    )
    (net (code "96") (name "unconnected-(P3-3.0-Pad1)") (class "Default")
      (node (ref "P3") (pin "1") (pinfunction "3.0_1") (pintype "passive"))
    )
    (net (code "97") (name "unconnected-(P3-3.1-Pad2)") (class "Default")
      (node (ref "P3") (pin "2") (pinfunction "3.1_2") (pintype "passive"))
    )
    (net (code "98") (name "unconnected-(P3-3.3-Pad4)") (class "Default")
      (node (ref "P3") (pin "4") (pinfunction "3.3_4") (pintype "passive"))
    )
    (net (code "99") (name "unconnected-(P3-3.4-Pad5)") (class "Default")
      (node (ref "P3") (pin "5") (pinfunction "3.4_5") (pintype "passive"))
    )
    (net (code "100") (name "unconnected-(P3-3.5-Pad6)") (class "Default")
      (node (ref "P3") (pin "6") (pinfunction "3.5_6") (pintype "passive"))
    )
    (net (code "101") (name "unconnected-(P3-3.6-Pad7)") (class "Default")
      (node (ref "P3") (pin "7") (pinfunction "3.6_7") (pintype "passive"))
    )
    (net (code "102") (name "unconnected-(P12-12.0-Pad1)") (class "Default")
      (node (ref "P12") (pin "1") (pinfunction "12.0_1") (pintype "passive"))
    )
    (net (code "103") (name "unconnected-(P12-12.1-Pad2)") (class "Default")
      (node (ref "P12") (pin "2") (pinfunction "12.1_2") (pintype "passive"))
    )
    (net (code "104") (name "unconnected-(P12-12.2-Pad3)") (class "Default")
      (node (ref "P12") (pin "3") (pinfunction "12.2_3") (pintype "passive"))
    )
    (net (code "105") (name "unconnected-(P12-12.3-Pad4)") (class "Default")
      (node (ref "P12") (pin "4") (pinfunction "12.3_4") (pintype "passive"))
    )
    (net (code "106") (name "unconnected-(P12-12.4-Pad5)") (class "Default")
      (node (ref "P12") (pin "5") (pinfunction "12.4_5") (pintype "passive"))
    )
    (net (code "107") (name "unconnected-(P12-12.5-Pad6)") (class "Default")
      (node (ref "P12") (pin "6") (pinfunction "12.5_6") (pintype "passive"))
    )
    (net (code "108") (name "unconnected-(P12-12.6-Pad7)") (class "Default")
      (node (ref "P12") (pin "7") (pinfunction "12.6_7") (pintype "passive"))
    )
    (net (code "109") (name "unconnected-(P12-12.7-Pad8)") (class "Default")
      (node (ref "P12") (pin "8") (pinfunction "12.7_8") (pintype "passive"))
    )
    (net (code "110") (name "unconnected-(P15-15.1-Pad2)") (class "Default")
      (node (ref "P15") (pin "2") (pinfunction "15.1_2") (pintype "passive"))
    )
    (net (code "111") (name "unconnected-(P15-15.2-Pad3)") (class "Default")
      (node (ref "P15") (pin "3") (pinfunction "15.2_3") (pintype "passive"))
    )
    (net (code "112") (name "unconnected-(P15-ENCD-Pad7)") (class "Default")
      (node (ref "P15") (pin "7") (pinfunction "ENCD_7") (pintype "passive"))
    )
    (net (code "113") (name "unconnected-(P15-ENCD-Pad8)") (class "Default")
      (node (ref "P15") (pin "8") (pinfunction "ENCD_8") (pintype "passive"))
    )
    (net (code "114") (name "unconnected-(R2-Pad1)") (class "Default")
      (node (ref "R2") (pin "1") (pinfunction "1_1") (pintype "passive"))
    )
    (net (code "115") (name "unconnected-(R3-Pad1)") (class "Default")
      (node (ref "R3") (pin "1") (pinfunction "1_1") (pintype "passive"))
    )
    (net (code "116") (name "unconnected-(R30-Pad1)") (class "Default")
      (node (ref "R30") (pin "1") (pinfunction "1_1") (pintype "passive"))
    )
  )
)
